# POWER_ANALOG.net
KiCad netlist of a schematic drawn in Altium Designer
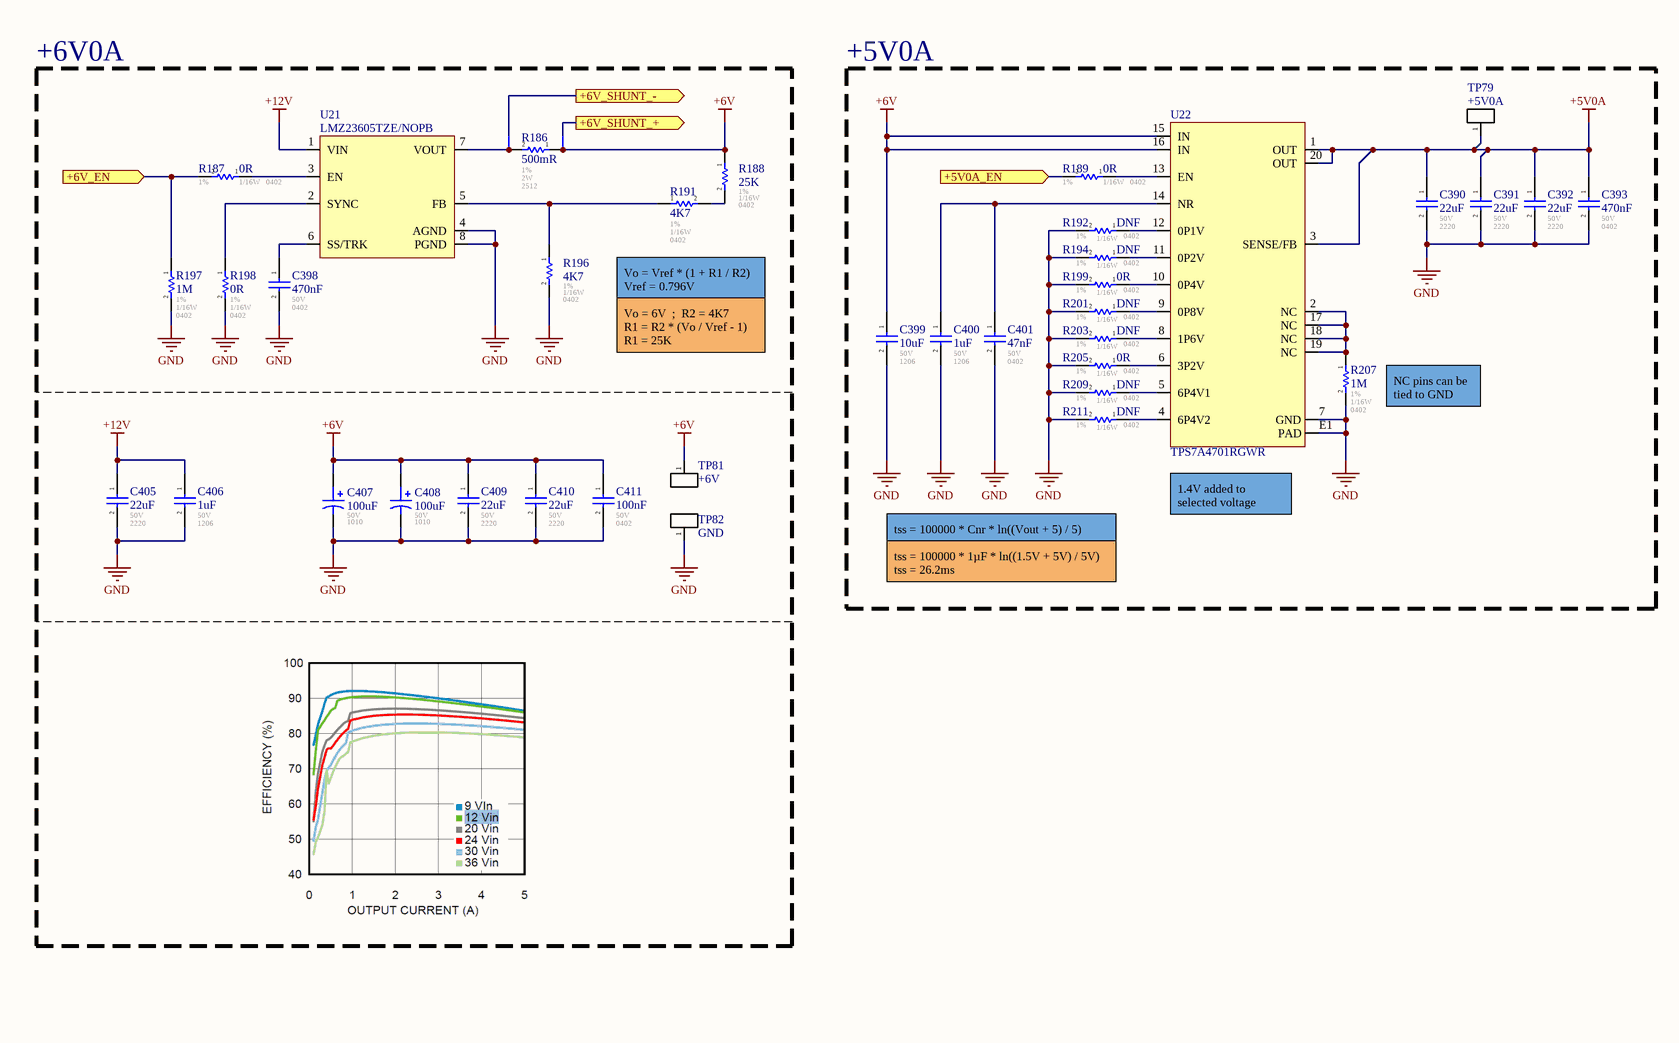
[diagram p0: POWER_ANALOG.SchDoc, top left]
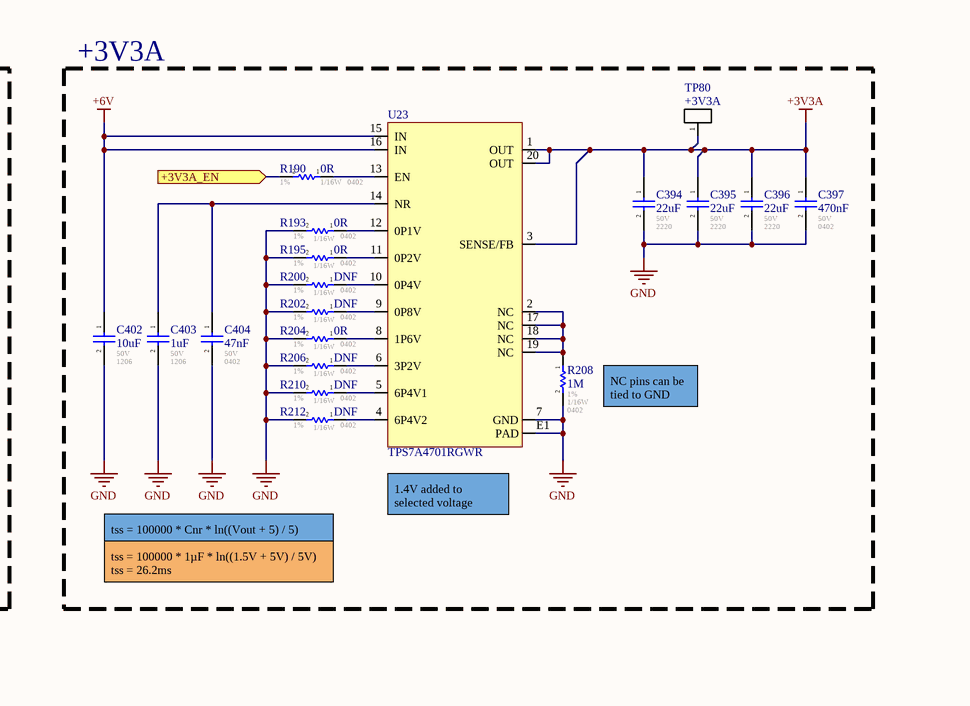
[diagram p1: POWER_ANALOG.SchDoc, top right]
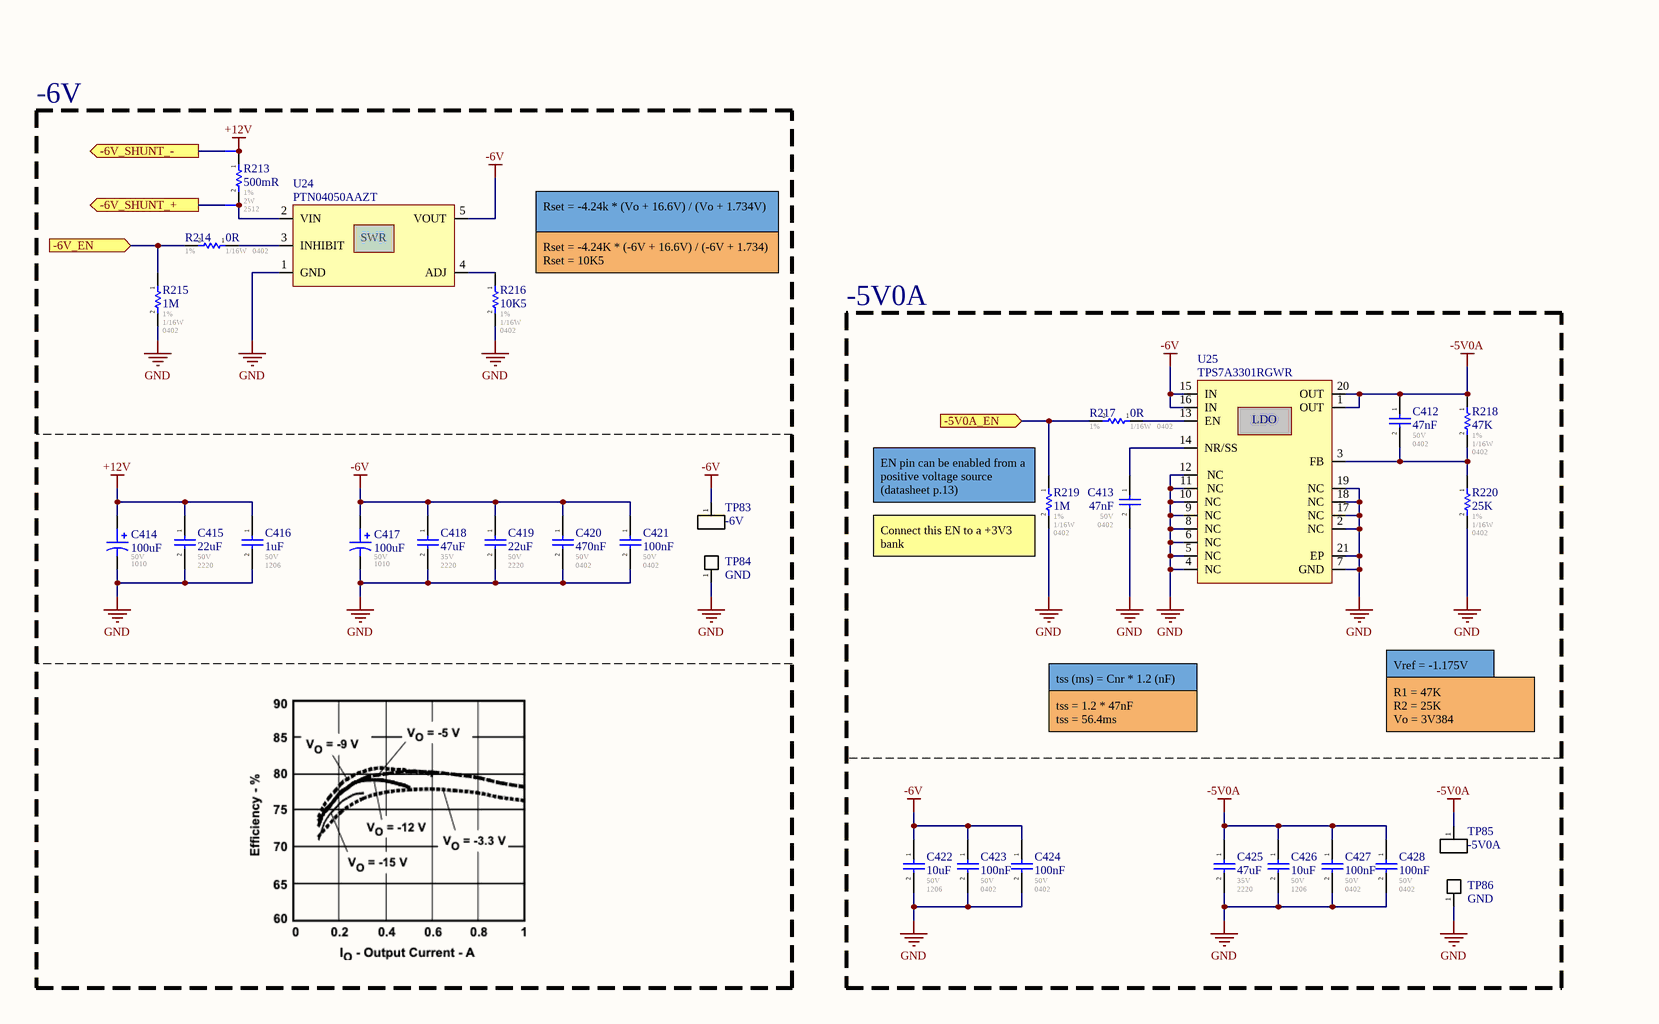
[diagram p2: POWER_ANALOG.SchDoc, bottom left]
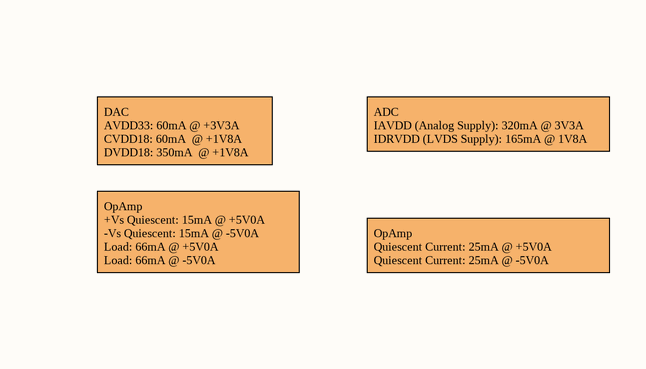
[diagram p3: POWER_ANALOG.SchDoc, bottom right]

(export (version "E")
  (design (tool "Eeschema 10.0.6"))
  (components
    (comp (ref "C390")
      (value "22uF")
      (footprint "2220")
      (description "CGA9P3X7R1H226M250KB\r\n2220 22uF 20% X7R Ceramic Capacitor")
      (fields
        (field (name "MFR") "TDK")
        (field (name "VOLTAGE - RATED") "50V")
        (field (name "TOLERANCE") "20%")
      )
      (libsource (lib "Symbols") (part "CAP_CER"))
    )
    (comp (ref "C391")
      (value "22uF")
      (footprint "2220")
      (description "CGA9P3X7R1H226M250KB\r\n2220 22uF 20% X7R Ceramic Capacitor")
      (fields
        (field (name "MFR") "TDK")
        (field (name "VOLTAGE - RATED") "50V")
        (field (name "TOLERANCE") "20%")
      )
      (libsource (lib "Symbols") (part "CAP_CER"))
    )
    (comp (ref "C392")
      (value "22uF")
      (footprint "2220")
      (description "CGA9P3X7R1H226M250KB\r\n2220 22uF 20% X7R Ceramic Capacitor")
      (fields
        (field (name "MFR") "TDK")
        (field (name "VOLTAGE - RATED") "50V")
        (field (name "TOLERANCE") "20%")
      )
      (libsource (lib "Symbols") (part "CAP_CER"))
    )
    (comp (ref "C393")
      (value "470nF")
      (footprint "0402")
      (description "CGA3E3X7R1H474K080AB\r\n0603 470nF 10% X7R Ceramic Capacitor")
      (fields
        (field (name "MFR") "TDK")
        (field (name "PART#") "CGA3E3X7R1H474K080AB")
        (field (name "VOLTAGE - RATED") "50V")
      )
      (libsource (lib "Symbols") (part "CAP_CER"))
    )
    (comp (ref "C394")
      (value "22uF")
      (footprint "2220")
      (description "CGA9P3X7R1H226M250KB\r\n2220 22uF 20% X7R Ceramic Capacitor")
      (fields
        (field (name "MFR") "TDK")
        (field (name "VOLTAGE - RATED") "50V")
        (field (name "TOLERANCE") "20%")
      )
      (libsource (lib "Symbols") (part "CAP_CER"))
    )
    (comp (ref "C395")
      (value "22uF")
      (footprint "2220")
      (description "CGA9P3X7R1H226M250KB\r\n2220 22uF 20% X7R Ceramic Capacitor")
      (fields
        (field (name "MFR") "TDK")
        (field (name "VOLTAGE - RATED") "50V")
        (field (name "TOLERANCE") "20%")
      )
      (libsource (lib "Symbols") (part "CAP_CER"))
    )
    (comp (ref "C396")
      (value "22uF")
      (footprint "2220")
      (description "CGA9P3X7R1H226M250KB\r\n2220 22uF 20% X7R Ceramic Capacitor")
      (fields
        (field (name "MFR") "TDK")
        (field (name "VOLTAGE - RATED") "50V")
        (field (name "TOLERANCE") "20%")
      )
      (libsource (lib "Symbols") (part "CAP_CER"))
    )
    (comp (ref "C397")
      (value "470nF")
      (footprint "0402")
      (description "CGA3E3X7R1H474K080AB\r\n0603 470nF 10% X7R Ceramic Capacitor")
      (fields
        (field (name "MFR") "TDK")
        (field (name "PART#") "CGA3E3X7R1H474K080AB")
        (field (name "VOLTAGE - RATED") "50V")
      )
      (libsource (lib "Symbols") (part "CAP_CER"))
    )
    (comp (ref "C398")
      (value "470nF")
      (footprint "0402")
      (description "CGA3E3X7R1H474K080AB\r\n0603 470nF 10% X7R Ceramic Capacitor")
      (fields
        (field (name "MFR") "TDK")
        (field (name "PART#") "CGA3E3X7R1H474K080AB")
        (field (name "VOLTAGE - RATED") "50V")
      )
      (libsource (lib "Symbols") (part "CAP_CER"))
    )
    (comp (ref "C399")
      (value "10uF")
      (footprint "1206")
      (description "GRT31CR61H106KE01L\r\n1206 10uF 10% X5R Ceramic Capacitor")
      (fields
        (field (name "MFR") "Murata")
        (field (name "VOLTAGE - RATED") "50V")
        (field (name "TOLERANCE") "10%")
      )
      (libsource (lib "Symbols") (part "CAP_CER"))
    )
    (comp (ref "C400")
      (value "1uF")
      (footprint "1206")
      (description "GCJ31CR71H105KA12L\r\n1206 1uF 10% X7R Ceramic Capacitor")
      (fields
        (field (name "MFR") "Murata")
        (field (name "PART#") "GCJ31CR71H105KA12L")
        (field (name "VOLTAGE - RATED") "50V")
      )
      (libsource (lib "Symbols") (part "CAP_CER"))
    )
    (comp (ref "C401")
      (value "47nF")
      (footprint "0402")
      (description "GCM155R71H473KE02J\r\n0402 47nF 10% X7R Ceramic Capacitor")
      (fields
        (field (name "MFR") "Murata")
        (field (name "PART#") "GCM155R71H473KE02J")
        (field (name "VOLTAGE - RATED") "50V")
      )
      (libsource (lib "Symbols") (part "CAP_CER"))
    )
    (comp (ref "C402")
      (value "10uF")
      (footprint "1206")
      (description "GRT31CR61H106KE01L\r\n1206 10uF 10% X5R Ceramic Capacitor")
      (fields
        (field (name "MFR") "Murata")
        (field (name "VOLTAGE - RATED") "50V")
        (field (name "TOLERANCE") "10%")
      )
      (libsource (lib "Symbols") (part "CAP_CER"))
    )
    (comp (ref "C403")
      (value "1uF")
      (footprint "1206")
      (description "GCJ31CR71H105KA12L\r\n1206 1uF 10% X7R Ceramic Capacitor")
      (fields
        (field (name "MFR") "Murata")
        (field (name "PART#") "GCJ31CR71H105KA12L")
        (field (name "VOLTAGE - RATED") "50V")
      )
      (libsource (lib "Symbols") (part "CAP_CER"))
    )
    (comp (ref "C404")
      (value "47nF")
      (footprint "0402")
      (description "GCM155R71H473KE02J\r\n0402 47nF 10% X7R Ceramic Capacitor")
      (fields
        (field (name "MFR") "Murata")
        (field (name "PART#") "GCM155R71H473KE02J")
        (field (name "VOLTAGE - RATED") "50V")
      )
      (libsource (lib "Symbols") (part "CAP_CER"))
    )
    (comp (ref "C405")
      (value "22uF")
      (footprint "2220")
      (description "CGA9P3X7R1H226M250KB\r\n2220 22uF 20% X7R Ceramic Capacitor")
      (fields
        (field (name "MFR") "TDK")
        (field (name "VOLTAGE - RATED") "50V")
        (field (name "TOLERANCE") "20%")
      )
      (libsource (lib "Symbols") (part "CAP_CER"))
    )
    (comp (ref "C406")
      (value "1uF")
      (footprint "1206")
      (description "GCJ31CR71H105KA12L\r\n1206 1uF 10% X7R Ceramic Capacitor")
      (fields
        (field (name "MFR") "Murata")
        (field (name "PART#") "GCJ31CR71H105KA12L")
        (field (name "VOLTAGE - RATED") "50V")
      )
      (libsource (lib "Symbols") (part "CAP_CER"))
    )
    (comp (ref "C407")
      (value "100uF")
      (footprint "CAP_ALU_1010_vishay")
      (description "CAP - ALU 100uF 20% 50V - 1010")
      (fields
        (field (name "MFG") "Vishay Dale")
        (field (name "MFG PART NUMBER") "MAL215099101E3")
        (field (name "VOLTAGE") "50V")
        (field (name "PACKAGE") "1010")
        (field (name "CREATEDBY") "Jonathan Bouchard")
      )
      (libsource (lib "S7CAS_LIB2023") (part "CAP_ALU_MAL215099101E3"))
    )
    (comp (ref "C408")
      (value "100uF")
      (footprint "CAP_ALU_1010_vishay")
      (description "CAP - ALU 100uF 20% 50V - 1010")
      (fields
        (field (name "MFG") "Vishay Dale")
        (field (name "MFG PART NUMBER") "MAL215099101E3")
        (field (name "VOLTAGE") "50V")
        (field (name "PACKAGE") "1010")
        (field (name "CREATEDBY") "Jonathan Bouchard")
      )
      (libsource (lib "S7CAS_LIB2023") (part "CAP_ALU_MAL215099101E3"))
    )
    (comp (ref "C409")
      (value "22uF")
      (footprint "2220")
      (description "CGA9P3X7R1H226M250KB\r\n2220 22uF 20% X7R Ceramic Capacitor")
      (fields
        (field (name "MFR") "TDK")
        (field (name "VOLTAGE - RATED") "50V")
        (field (name "TOLERANCE") "20%")
      )
      (libsource (lib "Symbols") (part "CAP_CER"))
    )
    (comp (ref "C410")
      (value "22uF")
      (footprint "2220")
      (description "CGA9P3X7R1H226M250KB\r\n2220 22uF 20% X7R Ceramic Capacitor")
      (fields
        (field (name "MFR") "TDK")
        (field (name "VOLTAGE - RATED") "50V")
        (field (name "TOLERANCE") "20%")
      )
      (libsource (lib "Symbols") (part "CAP_CER"))
    )
    (comp (ref "C411")
      (value "100nF")
      (footprint "0402")
      (description "GCM155R71H104KE02J\r\n0402 100nF 10% X7R Ceramic Capacitor")
      (fields
        (field (name "MFR") "Murata")
        (field (name "PART#") "GCM155R71H104KE02J")
        (field (name "VOLTAGE - RATED") "50V")
      )
      (libsource (lib "Symbols") (part "CAP_CER"))
    )
    (comp (ref "C412")
      (value "47nF")
      (footprint "0402")
      (description "GCM155R71H473KE02J\r\n0402 47nF 10% X7R Ceramic Capacitor")
      (fields
        (field (name "MFR") "Murata")
        (field (name "PART#") "GCM155R71H473KE02J")
        (field (name "VOLTAGE - RATED") "50V")
      )
      (libsource (lib "Symbols") (part "CAP_CER"))
    )
    (comp (ref "C413")
      (value "47nF")
      (footprint "0402")
      (description "GCM155R71H473KE02J\r\n0402 47nF 10% X7R Ceramic Capacitor")
      (fields
        (field (name "MFR") "Murata")
        (field (name "PART#") "GCM155R71H473KE02J")
        (field (name "VOLTAGE - RATED") "50V")
      )
      (libsource (lib "Symbols") (part "CAP_CER"))
    )
    (comp (ref "C414")
      (value "100uF")
      (footprint "CAP_ALU_1010_vishay")
      (description "CAP - ALU 100uF 20% 50V - 1010")
      (fields
        (field (name "MFG") "Vishay Dale")
        (field (name "MFG PART NUMBER") "MAL215099101E3")
        (field (name "VOLTAGE") "50V")
        (field (name "PACKAGE") "1010")
        (field (name "CREATEDBY") "Jonathan Bouchard")
      )
      (libsource (lib "S7CAS_LIB2023") (part "CAP_ALU_MAL215099101E3"))
    )
    (comp (ref "C415")
      (value "22uF")
      (footprint "2220")
      (description "CGA9P3X7R1H226M250KB\r\n2220 22uF 20% X7R Ceramic Capacitor")
      (fields
        (field (name "MFR") "TDK")
        (field (name "VOLTAGE - RATED") "50V")
        (field (name "TOLERANCE") "20%")
      )
      (libsource (lib "Symbols") (part "CAP_CER"))
    )
    (comp (ref "C416")
      (value "1uF")
      (footprint "1206")
      (description "GCJ31CR71H105KA12L\r\n1206 1uF 10% X7R Ceramic Capacitor")
      (fields
        (field (name "MFR") "Murata")
        (field (name "PART#") "GCJ31CR71H105KA12L")
        (field (name "VOLTAGE - RATED") "50V")
      )
      (libsource (lib "Symbols") (part "CAP_CER"))
    )
    (comp (ref "C417")
      (value "100uF")
      (footprint "CAP_ALU_1010_vishay")
      (description "CAP - ALU 100uF 20% 50V - 1010")
      (fields
        (field (name "MFG") "Vishay Dale")
        (field (name "MFG PART NUMBER") "MAL215099101E3")
        (field (name "VOLTAGE") "50V")
        (field (name "PACKAGE") "1010")
        (field (name "CREATEDBY") "Jonathan Bouchard")
      )
      (libsource (lib "S7CAS_LIB2023") (part "CAP_ALU_MAL215099101E3"))
    )
    (comp (ref "C418")
      (value "47uF")
      (footprint "2220")
      (description "CGA9N1X7R1V476M230KC\r\n2220 47uF 20% X7R Ceramic Capacitor")
      (fields
        (field (name "MFR") "TDK")
        (field (name "VOLTAGE - RATED") "35V")
        (field (name "TOLERANCE") "20%")
      )
      (libsource (lib "Symbols") (part "CAP_CER"))
    )
    (comp (ref "C419")
      (value "22uF")
      (footprint "2220")
      (description "CGA9P3X7R1H226M250KB\r\n2220 22uF 20% X7R Ceramic Capacitor")
      (fields
        (field (name "MFR") "TDK")
        (field (name "VOLTAGE - RATED") "50V")
        (field (name "TOLERANCE") "20%")
      )
      (libsource (lib "Symbols") (part "CAP_CER"))
    )
    (comp (ref "C420")
      (value "470nF")
      (footprint "0402")
      (description "CGA3E3X7R1H474K080AB\r\n0603 470nF 10% X7R Ceramic Capacitor")
      (fields
        (field (name "MFR") "TDK")
        (field (name "PART#") "CGA3E3X7R1H474K080AB")
        (field (name "VOLTAGE - RATED") "50V")
      )
      (libsource (lib "Symbols") (part "CAP_CER"))
    )
    (comp (ref "C421")
      (value "100nF")
      (footprint "0402")
      (description "GCM155R71H104KE02J\r\n0402 100nF 10% X7R Ceramic Capacitor")
      (fields
        (field (name "MFR") "Murata")
        (field (name "PART#") "GCM155R71H104KE02J")
        (field (name "VOLTAGE - RATED") "50V")
      )
      (libsource (lib "Symbols") (part "CAP_CER"))
    )
    (comp (ref "C422")
      (value "10uF")
      (footprint "1206")
      (description "GRT31CR61H106KE01L\r\n1206 10uF 10% X5R Ceramic Capacitor")
      (fields
        (field (name "MFR") "Murata")
        (field (name "VOLTAGE - RATED") "50V")
        (field (name "TOLERANCE") "10%")
      )
      (libsource (lib "Symbols") (part "CAP_CER"))
    )
    (comp (ref "C423")
      (value "100nF")
      (footprint "0402")
      (description "GCM155R71H104KE02J\r\n0402 100nF 10% X7R Ceramic Capacitor")
      (fields
        (field (name "MFR") "Murata")
        (field (name "PART#") "GCM155R71H104KE02J")
        (field (name "VOLTAGE - RATED") "50V")
      )
      (libsource (lib "Symbols") (part "CAP_CER"))
    )
    (comp (ref "C424")
      (value "100nF")
      (footprint "0402")
      (description "GCM155R71H104KE02J\r\n0402 100nF 10% X7R Ceramic Capacitor")
      (fields
        (field (name "MFR") "Murata")
        (field (name "PART#") "GCM155R71H104KE02J")
        (field (name "VOLTAGE - RATED") "50V")
      )
      (libsource (lib "Symbols") (part "CAP_CER"))
    )
    (comp (ref "C425")
      (value "47uF")
      (footprint "2220")
      (description "CGA9N1X7R1V476M230KC\r\n2220 47uF 20% X7R Ceramic Capacitor")
      (fields
        (field (name "MFR") "TDK")
        (field (name "VOLTAGE - RATED") "35V")
        (field (name "TOLERANCE") "20%")
      )
      (libsource (lib "Symbols") (part "CAP_CER"))
    )
    (comp (ref "C426")
      (value "10uF")
      (footprint "1206")
      (description "GRT31CR61H106KE01L\r\n1206 10uF 10% X5R Ceramic Capacitor")
      (fields
        (field (name "MFR") "Murata")
        (field (name "VOLTAGE - RATED") "50V")
        (field (name "TOLERANCE") "10%")
      )
      (libsource (lib "Symbols") (part "CAP_CER"))
    )
    (comp (ref "C427")
      (value "100nF")
      (footprint "0402")
      (description "GCM155R71H104KE02J\r\n0402 100nF 10% X7R Ceramic Capacitor")
      (fields
        (field (name "MFR") "Murata")
        (field (name "PART#") "GCM155R71H104KE02J")
        (field (name "VOLTAGE - RATED") "50V")
      )
      (libsource (lib "Symbols") (part "CAP_CER"))
    )
    (comp (ref "C428")
      (value "100nF")
      (footprint "0402")
      (description "GCM155R71H104KE02J\r\n0402 100nF 10% X7R Ceramic Capacitor")
      (fields
        (field (name "MFR") "Murata")
        (field (name "PART#") "GCM155R71H104KE02J")
        (field (name "VOLTAGE - RATED") "50V")
      )
      (libsource (lib "Symbols") (part "CAP_CER"))
    )
    (comp (ref "NT40")
      (value "Net Tie")
      (footprint "NETTIE_5")
      (libsource (lib "Symbols") (part "NET_TIE_SMALL"))
    )
    (comp (ref "NT41")
      (value "Net Tie")
      (footprint "NETTIE_5")
      (libsource (lib "Symbols") (part "NET_TIE_SMALL"))
    )
    (comp (ref "NT42")
      (value "Net Tie")
      (footprint "NETTIE_5")
      (libsource (lib "Symbols") (part "NET_TIE_SMALL"))
    )
    (comp (ref "NT43")
      (value "Net Tie")
      (footprint "NETTIE_5")
      (libsource (lib "Symbols") (part "NET_TIE_SMALL"))
    )
    (comp (ref "R186")
      (value "500mR")
      (footprint "RES_2512")
      (fields
        (field (name "PART #") "CSRN2512FKR500")
        (field (name "TOLERANCE") "1%")
        (field (name "POWER") "2W")
        (field (name "PACKAGE / CASE") "2512")
      )
      (libsource (lib "Symbols") (part "RESISTOR"))
    )
    (comp (ref "R187")
      (value "0R")
      (footprint "RES_0402")
      (fields
        (field (name "TOLERANCE") "1%")
        (field (name "POWER") "1/16W")
        (field (name "PACKAGE / CASE") "0402")
      )
      (libsource (lib "Symbols") (part "RESISTOR"))
    )
    (comp (ref "R188")
      (value "25K")
      (footprint "RES_0402")
      (fields
        (field (name "TOLERANCE") "1%")
        (field (name "POWER") "1/16W")
        (field (name "PACKAGE / CASE") "0402")
      )
      (libsource (lib "Symbols") (part "RESISTOR"))
    )
    (comp (ref "R189")
      (value "0R")
      (footprint "RES_0402")
      (fields
        (field (name "TOLERANCE") "1%")
        (field (name "POWER") "1/16W")
        (field (name "PACKAGE / CASE") "0402")
      )
      (libsource (lib "Symbols") (part "RESISTOR"))
    )
    (comp (ref "R190")
      (value "0R")
      (footprint "RES_0402")
      (fields
        (field (name "TOLERANCE") "1%")
        (field (name "POWER") "1/16W")
        (field (name "PACKAGE / CASE") "0402")
      )
      (libsource (lib "Symbols") (part "RESISTOR"))
    )
    (comp (ref "R191")
      (value "4K7")
      (footprint "RES_0402")
      (fields
        (field (name "TOLERANCE") "1%")
        (field (name "POWER") "1/16W")
        (field (name "PACKAGE / CASE") "0402")
      )
      (libsource (lib "Symbols") (part "RESISTOR"))
    )
    (comp (ref "R192")
      (value "DNF")
      (footprint "RES_0402")
      (fields
        (field (name "TOLERANCE") "1%")
        (field (name "POWER") "1/16W")
        (field (name "PACKAGE / CASE") "0402")
      )
      (libsource (lib "Symbols") (part "RESISTOR"))
    )
    (comp (ref "R193")
      (value "0R")
      (footprint "RES_0402")
      (fields
        (field (name "TOLERANCE") "1%")
        (field (name "POWER") "1/16W")
        (field (name "PACKAGE / CASE") "0402")
      )
      (libsource (lib "Symbols") (part "RESISTOR"))
    )
    (comp (ref "R194")
      (value "DNF")
      (footprint "RES_0402")
      (fields
        (field (name "TOLERANCE") "1%")
        (field (name "POWER") "1/16W")
        (field (name "PACKAGE / CASE") "0402")
      )
      (libsource (lib "Symbols") (part "RESISTOR"))
    )
    (comp (ref "R195")
      (value "0R")
      (footprint "RES_0402")
      (fields
        (field (name "TOLERANCE") "1%")
        (field (name "POWER") "1/16W")
        (field (name "PACKAGE / CASE") "0402")
      )
      (libsource (lib "Symbols") (part "RESISTOR"))
    )
    (comp (ref "R196")
      (value "4K7")
      (footprint "RES_0402")
      (fields
        (field (name "TOLERANCE") "1%")
        (field (name "POWER") "1/16W")
        (field (name "PACKAGE / CASE") "0402")
      )
      (libsource (lib "Symbols") (part "RESISTOR"))
    )
    (comp (ref "R197")
      (value "1M")
      (footprint "RES_0402")
      (description "1M 0402 1% 1/16W Resistor")
      (fields
        (field (name "TOLERANCE") "1%")
        (field (name "POWER") "1/16W")
        (field (name "PACKAGE / CASE") "0402")
      )
      (libsource (lib "Symbols") (part "RESISTOR"))
    )
    (comp (ref "R198")
      (value "0R")
      (footprint "RES_0402")
      (fields
        (field (name "TOLERANCE") "1%")
        (field (name "POWER") "1/16W")
        (field (name "PACKAGE / CASE") "0402")
      )
      (libsource (lib "Symbols") (part "RESISTOR"))
    )
    (comp (ref "R199")
      (value "0R")
      (footprint "RES_0402")
      (fields
        (field (name "TOLERANCE") "1%")
        (field (name "POWER") "1/16W")
        (field (name "PACKAGE / CASE") "0402")
      )
      (libsource (lib "Symbols") (part "RESISTOR"))
    )
    (comp (ref "R200")
      (value "DNF")
      (footprint "RES_0402")
      (fields
        (field (name "TOLERANCE") "1%")
        (field (name "POWER") "1/16W")
        (field (name "PACKAGE / CASE") "0402")
      )
      (libsource (lib "Symbols") (part "RESISTOR"))
    )
    (comp (ref "R201")
      (value "DNF")
      (footprint "RES_0402")
      (fields
        (field (name "TOLERANCE") "1%")
        (field (name "POWER") "1/16W")
        (field (name "PACKAGE / CASE") "0402")
      )
      (libsource (lib "Symbols") (part "RESISTOR"))
    )
    (comp (ref "R202")
      (value "DNF")
      (footprint "RES_0402")
      (fields
        (field (name "TOLERANCE") "1%")
        (field (name "POWER") "1/16W")
        (field (name "PACKAGE / CASE") "0402")
      )
      (libsource (lib "Symbols") (part "RESISTOR"))
    )
    (comp (ref "R203")
      (value "DNF")
      (footprint "RES_0402")
      (fields
        (field (name "TOLERANCE") "1%")
        (field (name "POWER") "1/16W")
        (field (name "PACKAGE / CASE") "0402")
      )
      (libsource (lib "Symbols") (part "RESISTOR"))
    )
    (comp (ref "R204")
      (value "0R")
      (footprint "RES_0402")
      (fields
        (field (name "TOLERANCE") "1%")
        (field (name "POWER") "1/16W")
        (field (name "PACKAGE / CASE") "0402")
      )
      (libsource (lib "Symbols") (part "RESISTOR"))
    )
    (comp (ref "R205")
      (value "0R")
      (footprint "RES_0402")
      (fields
        (field (name "TOLERANCE") "1%")
        (field (name "POWER") "1/16W")
        (field (name "PACKAGE / CASE") "0402")
      )
      (libsource (lib "Symbols") (part "RESISTOR"))
    )
    (comp (ref "R206")
      (value "DNF")
      (footprint "RES_0402")
      (fields
        (field (name "TOLERANCE") "1%")
        (field (name "POWER") "1/16W")
        (field (name "PACKAGE / CASE") "0402")
      )
      (libsource (lib "Symbols") (part "RESISTOR"))
    )
    (comp (ref "R207")
      (value "1M")
      (footprint "RES_0402")
      (description "1M 0402 1% 1/16W Resistor")
      (fields
        (field (name "TOLERANCE") "1%")
        (field (name "POWER") "1/16W")
        (field (name "PACKAGE / CASE") "0402")
      )
      (libsource (lib "Symbols") (part "RESISTOR"))
    )
    (comp (ref "R208")
      (value "1M")
      (footprint "RES_0402")
      (description "1M 0402 1% 1/16W Resistor")
      (fields
        (field (name "TOLERANCE") "1%")
        (field (name "POWER") "1/16W")
        (field (name "PACKAGE / CASE") "0402")
      )
      (libsource (lib "Symbols") (part "RESISTOR"))
    )
    (comp (ref "R209")
      (value "DNF")
      (footprint "RES_0402")
      (fields
        (field (name "TOLERANCE") "1%")
        (field (name "POWER") "1/16W")
        (field (name "PACKAGE / CASE") "0402")
      )
      (libsource (lib "Symbols") (part "RESISTOR"))
    )
    (comp (ref "R210")
      (value "DNF")
      (footprint "RES_0402")
      (fields
        (field (name "TOLERANCE") "1%")
        (field (name "POWER") "1/16W")
        (field (name "PACKAGE / CASE") "0402")
      )
      (libsource (lib "Symbols") (part "RESISTOR"))
    )
    (comp (ref "R211")
      (value "DNF")
      (footprint "RES_0402")
      (fields
        (field (name "TOLERANCE") "1%")
        (field (name "POWER") "1/16W")
        (field (name "PACKAGE / CASE") "0402")
      )
      (libsource (lib "Symbols") (part "RESISTOR"))
    )
    (comp (ref "R212")
      (value "DNF")
      (footprint "RES_0402")
      (fields
        (field (name "TOLERANCE") "1%")
        (field (name "POWER") "1/16W")
        (field (name "PACKAGE / CASE") "0402")
      )
      (libsource (lib "Symbols") (part "RESISTOR"))
    )
    (comp (ref "R213")
      (value "500mR")
      (footprint "RES_2512")
      (fields
        (field (name "PART #") "CSRN2512FKR500")
        (field (name "TOLERANCE") "1%")
        (field (name "POWER") "2W")
        (field (name "PACKAGE / CASE") "2512")
      )
      (libsource (lib "Symbols") (part "RESISTOR"))
    )
    (comp (ref "R214")
      (value "0R")
      (footprint "RES_0402")
      (fields
        (field (name "TOLERANCE") "1%")
        (field (name "POWER") "1/16W")
        (field (name "PACKAGE / CASE") "0402")
      )
      (libsource (lib "Symbols") (part "RESISTOR"))
    )
    (comp (ref "R215")
      (value "1M")
      (footprint "RES_0402")
      (description "1M 0402 1% 1/16W Resistor")
      (fields
        (field (name "TOLERANCE") "1%")
        (field (name "POWER") "1/16W")
        (field (name "PACKAGE / CASE") "0402")
      )
      (libsource (lib "Symbols") (part "RESISTOR"))
    )
    (comp (ref "R216")
      (value "10K5")
      (footprint "RES_0402")
      (fields
        (field (name "TOLERANCE") "1%")
        (field (name "POWER") "1/16W")
        (field (name "PACKAGE / CASE") "0402")
      )
      (libsource (lib "Symbols") (part "RESISTOR"))
    )
    (comp (ref "R217")
      (value "0R")
      (footprint "RES_0402")
      (fields
        (field (name "TOLERANCE") "1%")
        (field (name "POWER") "1/16W")
        (field (name "PACKAGE / CASE") "0402")
      )
      (libsource (lib "Symbols") (part "RESISTOR"))
    )
    (comp (ref "R218")
      (value "47K")
      (footprint "RES_0402")
      (fields
        (field (name "TOLERANCE") "1%")
        (field (name "POWER") "1/16W")
        (field (name "PACKAGE / CASE") "0402")
      )
      (libsource (lib "Symbols") (part "RESISTOR"))
    )
    (comp (ref "R219")
      (value "1M")
      (footprint "RES_0402")
      (description "1M 0402 1% 1/16W Resistor")
      (fields
        (field (name "TOLERANCE") "1%")
        (field (name "POWER") "1/16W")
        (field (name "PACKAGE / CASE") "0402")
      )
      (libsource (lib "Symbols") (part "RESISTOR"))
    )
    (comp (ref "R220")
      (value "25K")
      (footprint "RES_0402")
      (fields
        (field (name "TOLERANCE") "1%")
        (field (name "POWER") "1/16W")
        (field (name "PACKAGE / CASE") "0402")
      )
      (libsource (lib "Symbols") (part "RESISTOR"))
    )
    (comp (ref "TP79")
      (value "+5V0A")
      (footprint "TP_HOLE")
      (description "Test Point")
      (libsource (lib "Symbols") (part "TESTPOINT"))
    )
    (comp (ref "TP80")
      (value "+3V3A")
      (footprint "TP_HOLE")
      (description "Test Point")
      (libsource (lib "Symbols") (part "TESTPOINT"))
    )
    (comp (ref "TP81")
      (value "+6V")
      (footprint "TP_HOLE")
      (description "Test Point")
      (libsource (lib "Symbols") (part "TESTPOINT"))
    )
    (comp (ref "TP82")
      (value "GND")
      (footprint "TP_HOLE")
      (description "Test Point")
      (libsource (lib "Symbols") (part "TESTPOINT"))
    )
    (comp (ref "TP83")
      (value "-6V")
      (footprint "TP_HOLE")
      (description "Test Point")
      (libsource (lib "Symbols") (part "TESTPOINT"))
    )
    (comp (ref "TP84")
      (value "GND")
      (footprint "TP_PAD")
      (description "Test Point")
      (libsource (lib "Symbols") (part "TESTPOINT_PAD"))
    )
    (comp (ref "TP85")
      (value "-5V0A")
      (footprint "TP_HOLE")
      (description "Test Point")
      (libsource (lib "Symbols") (part "TESTPOINT"))
    )
    (comp (ref "TP86")
      (value "GND")
      (footprint "TP_PAD")
      (description "Test Point")
      (libsource (lib "Symbols") (part "TESTPOINT_PAD"))
    )
    (comp (ref "U21")
      (value "LMZ23605TZE/NOPB")
      (footprint "REG_SWR_LMZ23605TZE/NOPB")
      (description "REG - IC BUCK SYNC 36V 5A - TO-PMOD-7")
      (fields
        (field (name "CREATEDBY/DATE") "Arnaud Samson - 05/07/18")
        (field (name "VERIFIEDBY") "Jonathan Bouchard 2018-07-13")
      )
      (libsource (lib "S7CAS_LIB2023") (part "REG_SWR_LMZ23605TZE/NOPB"))
    )
    (comp (ref "U22")
      (value "TPS7A4701RGWR")
      (footprint "REG_TPS7A4701RGWR")
      (description "REG - LINEAR POS ADJ 1A - 20VQFN")
      (fields
        (field (name "CREATEDBY/DATE") "L-P Gauthier / 2018-05-29")
        (field (name "VERIFIEDBY") "Caroline Paulin - 28 sept 2018")
      )
      (libsource (lib "S7CAS_LIB2023") (part "REG_LDO_TPS7A4701RGWR"))
    )
    (comp (ref "U23")
      (value "TPS7A4701RGWR")
      (footprint "REG_TPS7A4701RGWR")
      (description "REG - LINEAR POS ADJ 1A - 20VQFN")
      (fields
        (field (name "CREATEDBY/DATE") "L-P Gauthier / 2018-05-29")
        (field (name "VERIFIEDBY") "Caroline Paulin - 28 sept 2018")
      )
      (libsource (lib "S7CAS_LIB2023") (part "REG_LDO_TPS7A4701RGWR"))
    )
    (comp (ref "U24")
      (value "PTN04050AAZT")
      (footprint "REG_SWR_PTN04050AAZT")
      (description "REG - SWR -15 ~ -3.3V 1A 6W - 5-SMD")
      (fields
        (field (name "CREATEDBY/DATE") "Ihsane Najahi 2019-09-25")
        (field (name "VERIFIEDBY") "C.Paulin (9-10-2019)")
      )
      (libsource (lib "S7CAS_LIB2023") (part "REG_SWR_PTN04050AAZT"))
    )
    (comp (ref "U25")
      (value "TPS7A3301RGWR")
      (footprint "REG_LDO_TPS7A3301RGWR")
      (description "REG - LDO Negative Adjustable 1 Output -1.18V-33V 1A -  20-VQFN (5x5)")
      (fields
        (field (name "CREATEDBY/DATE") "Keven Deslandes - 2018/10/11")
        (field (name "VERIFIEDBY") "Caroline Paulin - 11/12/2018")
      )
      (libsource (lib "S7CAS_LIB2023") (part "REG_LDO_TPS7A3301RGWR"))
    )
  )
  (nets
    (net (code "1") (name "+3V3A") (class "Default")
      (node (ref "C394") (pin "1") (pinfunction "1_1") (pintype "passive"))
      (node (ref "C395") (pin "1") (pinfunction "1_1") (pintype "passive"))
      (node (ref "C396") (pin "1") (pinfunction "1_1") (pintype "passive"))
      (node (ref "C397") (pin "1") (pinfunction "1_1") (pintype "passive"))
      (node (ref "TP80") (pin "1") (pinfunction "A_1") (pintype "passive"))
      (node (ref "U23") (pin "1") (pinfunction "OUT_1") (pintype "passive"))
      (node (ref "U23") (pin "20") (pinfunction "OUT_20") (pintype "passive"))
      (node (ref "U23") (pin "3") (pinfunction "SENSE/FB_3") (pintype "passive"))
    )
    (net (code "2") (name "+5V0A") (class "Default")
      (node (ref "C390") (pin "1") (pinfunction "1_1") (pintype "passive"))
      (node (ref "C391") (pin "1") (pinfunction "1_1") (pintype "passive"))
      (node (ref "C392") (pin "1") (pinfunction "1_1") (pintype "passive"))
      (node (ref "C393") (pin "1") (pinfunction "1_1") (pintype "passive"))
      (node (ref "TP79") (pin "1") (pinfunction "A_1") (pintype "passive"))
      (node (ref "U22") (pin "1") (pinfunction "OUT_1") (pintype "passive"))
      (node (ref "U22") (pin "20") (pinfunction "OUT_20") (pintype "passive"))
      (node (ref "U22") (pin "3") (pinfunction "SENSE/FB_3") (pintype "passive"))
    )
    (net (code "3") (name "+6V") (class "Default")
      (node (ref "C399") (pin "1") (pinfunction "1_1") (pintype "passive"))
      (node (ref "C402") (pin "1") (pinfunction "1_1") (pintype "passive"))
      (node (ref "C407") (pin "1") (pinfunction "1_1") (pintype "passive"))
      (node (ref "C408") (pin "1") (pinfunction "1_1") (pintype "passive"))
      (node (ref "C409") (pin "1") (pinfunction "1_1") (pintype "passive"))
      (node (ref "C410") (pin "1") (pinfunction "1_1") (pintype "passive"))
      (node (ref "C411") (pin "1") (pinfunction "1_1") (pintype "passive"))
      (node (ref "NT41") (pin "1") (pinfunction "1_1") (pintype "passive"))
      (node (ref "R186") (pin "1") (pinfunction "1_1") (pintype "passive"))
      (node (ref "R188") (pin "1") (pinfunction "1_1") (pintype "passive"))
      (node (ref "TP81") (pin "1") (pinfunction "A_1") (pintype "passive"))
      (node (ref "U22") (pin "15") (pinfunction "IN_15") (pintype "passive"))
      (node (ref "U22") (pin "16") (pinfunction "IN_16") (pintype "passive"))
      (node (ref "U23") (pin "15") (pinfunction "IN_15") (pintype "passive"))
      (node (ref "U23") (pin "16") (pinfunction "IN_16") (pintype "passive"))
    )
    (net (code "4") (name "+12V") (class "Default")
      (node (ref "C405") (pin "1") (pinfunction "1_1") (pintype "passive"))
      (node (ref "C406") (pin "1") (pinfunction "1_1") (pintype "passive"))
      (node (ref "C414") (pin "1") (pinfunction "1_1") (pintype "passive"))
      (node (ref "C415") (pin "1") (pinfunction "1_1") (pintype "passive"))
      (node (ref "C416") (pin "1") (pinfunction "1_1") (pintype "passive"))
      (node (ref "NT42") (pin "1") (pinfunction "1_1") (pintype "passive"))
      (node (ref "R213") (pin "1") (pinfunction "1_1") (pintype "passive"))
      (node (ref "U21") (pin "1") (pinfunction "VIN_1") (pintype "passive"))
    )
    (net (code "5") (name "-5V0A") (class "Default")
      (node (ref "C412") (pin "1") (pinfunction "1_1") (pintype "passive"))
      (node (ref "C425") (pin "1") (pinfunction "1_1") (pintype "passive"))
      (node (ref "C426") (pin "1") (pinfunction "1_1") (pintype "passive"))
      (node (ref "C427") (pin "1") (pinfunction "1_1") (pintype "passive"))
      (node (ref "C428") (pin "1") (pinfunction "1_1") (pintype "passive"))
      (node (ref "R218") (pin "1") (pinfunction "1_1") (pintype "passive"))
      (node (ref "TP85") (pin "1") (pinfunction "A_1") (pintype "passive"))
      (node (ref "U25") (pin "1") (pinfunction "OUT_1") (pintype "passive"))
      (node (ref "U25") (pin "20") (pinfunction "OUT_20") (pintype "passive"))
    )
    (net (code "6") (name "-6V") (class "Default")
      (node (ref "C417") (pin "1") (pinfunction "1_1") (pintype "passive"))
      (node (ref "C418") (pin "1") (pinfunction "1_1") (pintype "passive"))
      (node (ref "C419") (pin "1") (pinfunction "1_1") (pintype "passive"))
      (node (ref "C420") (pin "1") (pinfunction "1_1") (pintype "passive"))
      (node (ref "C421") (pin "1") (pinfunction "1_1") (pintype "passive"))
      (node (ref "C422") (pin "1") (pinfunction "1_1") (pintype "passive"))
      (node (ref "C423") (pin "1") (pinfunction "1_1") (pintype "passive"))
      (node (ref "C424") (pin "1") (pinfunction "1_1") (pintype "passive"))
      (node (ref "TP83") (pin "1") (pinfunction "A_1") (pintype "passive"))
      (node (ref "U24") (pin "5") (pinfunction "VOUT_5") (pintype "passive"))
      (node (ref "U25") (pin "15") (pinfunction "IN_15") (pintype "passive"))
      (node (ref "U25") (pin "16") (pinfunction "IN_16") (pintype "passive"))
    )
    (net (code "7") (name "/+3V3A_EN") (class "Default")
      (node (ref "R190") (pin "2") (pinfunction "2_2") (pintype "passive"))
    )
    (net (code "8") (name "/+5V0A_EN") (class "Default")
      (node (ref "R189") (pin "2") (pinfunction "2_2") (pintype "passive"))
    )
    (net (code "9") (name "/+6V_EN") (class "Default")
      (node (ref "R187") (pin "2") (pinfunction "2_2") (pintype "passive"))
      (node (ref "R197") (pin "1") (pinfunction "1_1") (pintype "passive"))
    )
    (net (code "10") (name "/+6V_SHUNT_+") (class "Default")
      (node (ref "NT41") (pin "2") (pinfunction "2_2") (pintype "passive"))
    )
    (net (code "11") (name "/+6V_SHUNT_-") (class "Default")
      (node (ref "NT40") (pin "2") (pinfunction "2_2") (pintype "passive"))
    )
    (net (code "12") (name "/-5V0A_EN") (class "Default")
      (node (ref "R217") (pin "2") (pinfunction "2_2") (pintype "passive"))
      (node (ref "R219") (pin "1") (pinfunction "1_1") (pintype "passive"))
    )
    (net (code "13") (name "/-6V_EN") (class "Default")
      (node (ref "R214") (pin "2") (pinfunction "2_2") (pintype "passive"))
      (node (ref "R215") (pin "1") (pinfunction "1_1") (pintype "passive"))
    )
    (net (code "14") (name "/-6V_SHUNT_+") (class "Default")
      (node (ref "NT43") (pin "2") (pinfunction "2_2") (pintype "passive"))
    )
    (net (code "15") (name "/-6V_SHUNT_-") (class "Default")
      (node (ref "NT42") (pin "2") (pinfunction "2_2") (pintype "passive"))
    )
    (net (code "16") (name "GND") (class "Default")
      (node (ref "C390") (pin "2") (pinfunction "2_2") (pintype "passive"))
      (node (ref "C391") (pin "2") (pinfunction "2_2") (pintype "passive"))
      (node (ref "C392") (pin "2") (pinfunction "2_2") (pintype "passive"))
      (node (ref "C393") (pin "2") (pinfunction "2_2") (pintype "passive"))
      (node (ref "C394") (pin "2") (pinfunction "2_2") (pintype "passive"))
      (node (ref "C395") (pin "2") (pinfunction "2_2") (pintype "passive"))
      (node (ref "C396") (pin "2") (pinfunction "2_2") (pintype "passive"))
      (node (ref "C397") (pin "2") (pinfunction "2_2") (pintype "passive"))
      (node (ref "C398") (pin "2") (pinfunction "2_2") (pintype "passive"))
      (node (ref "C399") (pin "2") (pinfunction "2_2") (pintype "passive"))
      (node (ref "C400") (pin "2") (pinfunction "2_2") (pintype "passive"))
      (node (ref "C401") (pin "2") (pinfunction "2_2") (pintype "passive"))
      (node (ref "C402") (pin "2") (pinfunction "2_2") (pintype "passive"))
      (node (ref "C403") (pin "2") (pinfunction "2_2") (pintype "passive"))
      (node (ref "C404") (pin "2") (pinfunction "2_2") (pintype "passive"))
      (node (ref "C405") (pin "2") (pinfunction "2_2") (pintype "passive"))
      (node (ref "C406") (pin "2") (pinfunction "2_2") (pintype "passive"))
      (node (ref "C407") (pin "2") (pinfunction "2_2") (pintype "passive"))
      (node (ref "C408") (pin "2") (pinfunction "2_2") (pintype "passive"))
      (node (ref "C409") (pin "2") (pinfunction "2_2") (pintype "passive"))
      (node (ref "C410") (pin "2") (pinfunction "2_2") (pintype "passive"))
      (node (ref "C411") (pin "2") (pinfunction "2_2") (pintype "passive"))
      (node (ref "C413") (pin "2") (pinfunction "2_2") (pintype "passive"))
      (node (ref "C414") (pin "2") (pinfunction "2_2") (pintype "passive"))
      (node (ref "C415") (pin "2") (pinfunction "2_2") (pintype "passive"))
      (node (ref "C416") (pin "2") (pinfunction "2_2") (pintype "passive"))
      (node (ref "C417") (pin "2") (pinfunction "2_2") (pintype "passive"))
      (node (ref "C418") (pin "2") (pinfunction "2_2") (pintype "passive"))
      (node (ref "C419") (pin "2") (pinfunction "2_2") (pintype "passive"))
      (node (ref "C420") (pin "2") (pinfunction "2_2") (pintype "passive"))
      (node (ref "C421") (pin "2") (pinfunction "2_2") (pintype "passive"))
      (node (ref "C422") (pin "2") (pinfunction "2_2") (pintype "passive"))
      (node (ref "C423") (pin "2") (pinfunction "2_2") (pintype "passive"))
      (node (ref "C424") (pin "2") (pinfunction "2_2") (pintype "passive"))
      (node (ref "C425") (pin "2") (pinfunction "2_2") (pintype "passive"))
      (node (ref "C426") (pin "2") (pinfunction "2_2") (pintype "passive"))
      (node (ref "C427") (pin "2") (pinfunction "2_2") (pintype "passive"))
      (node (ref "C428") (pin "2") (pinfunction "2_2") (pintype "passive"))
      (node (ref "R192") (pin "2") (pinfunction "2_2") (pintype "passive"))
      (node (ref "R193") (pin "2") (pinfunction "2_2") (pintype "passive"))
      (node (ref "R194") (pin "2") (pinfunction "2_2") (pintype "passive"))
      (node (ref "R195") (pin "2") (pinfunction "2_2") (pintype "passive"))
      (node (ref "R196") (pin "2") (pinfunction "2_2") (pintype "passive"))
      (node (ref "R197") (pin "2") (pinfunction "2_2") (pintype "passive"))
      (node (ref "R198") (pin "2") (pinfunction "2_2") (pintype "passive"))
      (node (ref "R199") (pin "2") (pinfunction "2_2") (pintype "passive"))
      (node (ref "R200") (pin "2") (pinfunction "2_2") (pintype "passive"))
      (node (ref "R201") (pin "2") (pinfunction "2_2") (pintype "passive"))
      (node (ref "R202") (pin "2") (pinfunction "2_2") (pintype "passive"))
      (node (ref "R203") (pin "2") (pinfunction "2_2") (pintype "passive"))
      (node (ref "R204") (pin "2") (pinfunction "2_2") (pintype "passive"))
      (node (ref "R205") (pin "2") (pinfunction "2_2") (pintype "passive"))
      (node (ref "R206") (pin "2") (pinfunction "2_2") (pintype "passive"))
      (node (ref "R207") (pin "2") (pinfunction "2_2") (pintype "passive"))
      (node (ref "R208") (pin "2") (pinfunction "2_2") (pintype "passive"))
      (node (ref "R209") (pin "2") (pinfunction "2_2") (pintype "passive"))
      (node (ref "R210") (pin "2") (pinfunction "2_2") (pintype "passive"))
      (node (ref "R211") (pin "2") (pinfunction "2_2") (pintype "passive"))
      (node (ref "R212") (pin "2") (pinfunction "2_2") (pintype "passive"))
      (node (ref "R215") (pin "2") (pinfunction "2_2") (pintype "passive"))
      (node (ref "R216") (pin "2") (pinfunction "2_2") (pintype "passive"))
      (node (ref "R219") (pin "2") (pinfunction "2_2") (pintype "passive"))
      (node (ref "R220") (pin "2") (pinfunction "2_2") (pintype "passive"))
      (node (ref "TP82") (pin "1") (pinfunction "A_1") (pintype "passive"))
      (node (ref "TP84") (pin "1") (pinfunction "A_1") (pintype "passive"))
      (node (ref "TP86") (pin "1") (pinfunction "A_1") (pintype "passive"))
      (node (ref "U21") (pin "4") (pinfunction "AGND_4") (pintype "passive"))
      (node (ref "U21") (pin "8") (pinfunction "PGND_8") (pintype "passive"))
      (node (ref "U22") (pin "7") (pinfunction "GND_7") (pintype "passive"))
      (node (ref "U22") (pin "E1") (pinfunction "PAD_E1") (pintype "passive"))
      (node (ref "U23") (pin "7") (pinfunction "GND_7") (pintype "passive"))
      (node (ref "U23") (pin "E1") (pinfunction "PAD_E1") (pintype "passive"))
      (node (ref "U24") (pin "1") (pinfunction "GND_1") (pintype "passive"))
      (node (ref "U25") (pin "10") (pinfunction "NC_10") (pintype "passive"))
      (node (ref "U25") (pin "11") (pinfunction "NC_11") (pintype "passive"))
      (node (ref "U25") (pin "12") (pinfunction "NC_12") (pintype "passive"))
      (node (ref "U25") (pin "17") (pinfunction "NC_17") (pintype "passive"))
      (node (ref "U25") (pin "18") (pinfunction "NC_18") (pintype "passive"))
      (node (ref "U25") (pin "19") (pinfunction "NC_19") (pintype "passive"))
      (node (ref "U25") (pin "2") (pinfunction "NC_2") (pintype "passive"))
      (node (ref "U25") (pin "21") (pinfunction "EP_21") (pintype "passive"))
      (node (ref "U25") (pin "4") (pinfunction "NC_4") (pintype "passive"))
      (node (ref "U25") (pin "5") (pinfunction "NC_5") (pintype "passive"))
      (node (ref "U25") (pin "6") (pinfunction "NC_6") (pintype "passive"))
      (node (ref "U25") (pin "7") (pinfunction "GND_7") (pintype "passive"))
      (node (ref "U25") (pin "8") (pinfunction "NC_8") (pintype "passive"))
      (node (ref "U25") (pin "9") (pinfunction "NC_9") (pintype "passive"))
    )
    (net (code "17") (name "Net-(R188-Pad2)") (class "Default")
      (node (ref "R188") (pin "2") (pinfunction "2_2") (pintype "passive"))
      (node (ref "R191") (pin "2") (pinfunction "2_2") (pintype "passive"))
    )
    (net (code "18") (name "Net-(R207-Pad1)") (class "Default")
      (node (ref "R207") (pin "1") (pinfunction "1_1") (pintype "passive"))
      (node (ref "U22") (pin "17") (pinfunction "NC_17") (pintype "passive"))
      (node (ref "U22") (pin "18") (pinfunction "NC_18") (pintype "passive"))
      (node (ref "U22") (pin "19") (pinfunction "NC_19") (pintype "passive"))
      (node (ref "U22") (pin "2") (pinfunction "NC_2") (pintype "passive"))
    )
    (net (code "19") (name "Net-(R208-Pad1)") (class "Default")
      (node (ref "R208") (pin "1") (pinfunction "1_1") (pintype "passive"))
      (node (ref "U23") (pin "17") (pinfunction "NC_17") (pintype "passive"))
      (node (ref "U23") (pin "18") (pinfunction "NC_18") (pintype "passive"))
      (node (ref "U23") (pin "19") (pinfunction "NC_19") (pintype "passive"))
      (node (ref "U23") (pin "2") (pinfunction "NC_2") (pintype "passive"))
    )
    (net (code "20") (name "Net-(U21-EN)") (class "Default")
      (node (ref "R187") (pin "1") (pinfunction "1_1") (pintype "passive"))
      (node (ref "U21") (pin "3") (pinfunction "EN_3") (pintype "passive"))
    )
    (net (code "21") (name "Net-(U21-FB)") (class "Default")
      (node (ref "R191") (pin "1") (pinfunction "1_1") (pintype "passive"))
      (node (ref "R196") (pin "1") (pinfunction "1_1") (pintype "passive"))
      (node (ref "U21") (pin "5") (pinfunction "FB_5") (pintype "passive"))
    )
    (net (code "22") (name "Net-(U21-SS{slash}TRK)") (class "Default")
      (node (ref "C398") (pin "1") (pinfunction "1_1") (pintype "passive"))
      (node (ref "U21") (pin "6") (pinfunction "SS/TRK_6") (pintype "passive"))
    )
    (net (code "23") (name "Net-(U21-SYNC)") (class "Default")
      (node (ref "R198") (pin "1") (pinfunction "1_1") (pintype "passive"))
      (node (ref "U21") (pin "2") (pinfunction "SYNC_2") (pintype "passive"))
    )
    (net (code "24") (name "Net-(U21-VOUT)") (class "Default")
      (node (ref "NT40") (pin "1") (pinfunction "1_1") (pintype "passive"))
      (node (ref "R186") (pin "2") (pinfunction "2_2") (pintype "passive"))
      (node (ref "U21") (pin "7") (pinfunction "VOUT_7") (pintype "passive"))
    )
    (net (code "25") (name "Net-(U22-0P1V)") (class "Default")
      (node (ref "R192") (pin "1") (pinfunction "1_1") (pintype "passive"))
      (node (ref "U22") (pin "12") (pinfunction "0P1V_12") (pintype "passive"))
    )
    (net (code "26") (name "Net-(U22-0P2V)") (class "Default")
      (node (ref "R194") (pin "1") (pinfunction "1_1") (pintype "passive"))
      (node (ref "U22") (pin "11") (pinfunction "0P2V_11") (pintype "passive"))
    )
    (net (code "27") (name "Net-(U22-0P4V)") (class "Default")
      (node (ref "R199") (pin "1") (pinfunction "1_1") (pintype "passive"))
      (node (ref "U22") (pin "10") (pinfunction "0P4V_10") (pintype "passive"))
    )
    (net (code "28") (name "Net-(U22-0P8V)") (class "Default")
      (node (ref "R201") (pin "1") (pinfunction "1_1") (pintype "passive"))
      (node (ref "U22") (pin "9") (pinfunction "0P8V_9") (pintype "passive"))
    )
    (net (code "29") (name "Net-(U22-1P6V)") (class "Default")
      (node (ref "R203") (pin "1") (pinfunction "1_1") (pintype "passive"))
      (node (ref "U22") (pin "8") (pinfunction "1P6V_8") (pintype "passive"))
    )
    (net (code "30") (name "Net-(U22-3P2V)") (class "Default")
      (node (ref "R205") (pin "1") (pinfunction "1_1") (pintype "passive"))
      (node (ref "U22") (pin "6") (pinfunction "3P2V_6") (pintype "passive"))
    )
    (net (code "31") (name "Net-(U22-6P4V1)") (class "Default")
      (node (ref "R209") (pin "1") (pinfunction "1_1") (pintype "passive"))
      (node (ref "U22") (pin "5") (pinfunction "6P4V1_5") (pintype "passive"))
    )
    (net (code "32") (name "Net-(U22-6P4V2)") (class "Default")
      (node (ref "R211") (pin "1") (pinfunction "1_1") (pintype "passive"))
      (node (ref "U22") (pin "4") (pinfunction "6P4V2_4") (pintype "passive"))
    )
    (net (code "33") (name "Net-(U22-EN)") (class "Default")
      (node (ref "R189") (pin "1") (pinfunction "1_1") (pintype "passive"))
      (node (ref "U22") (pin "13") (pinfunction "EN_13") (pintype "passive"))
    )
    (net (code "34") (name "Net-(U22-NR)") (class "Default")
      (node (ref "C400") (pin "1") (pinfunction "1_1") (pintype "passive"))
      (node (ref "C401") (pin "1") (pinfunction "1_1") (pintype "passive"))
      (node (ref "U22") (pin "14") (pinfunction "NR_14") (pintype "passive"))
    )
    (net (code "35") (name "Net-(U23-0P1V)") (class "Default")
      (node (ref "R193") (pin "1") (pinfunction "1_1") (pintype "passive"))
      (node (ref "U23") (pin "12") (pinfunction "0P1V_12") (pintype "passive"))
    )
    (net (code "36") (name "Net-(U23-0P2V)") (class "Default")
      (node (ref "R195") (pin "1") (pinfunction "1_1") (pintype "passive"))
      (node (ref "U23") (pin "11") (pinfunction "0P2V_11") (pintype "passive"))
    )
    (net (code "37") (name "Net-(U23-0P4V)") (class "Default")
      (node (ref "R200") (pin "1") (pinfunction "1_1") (pintype "passive"))
      (node (ref "U23") (pin "10") (pinfunction "0P4V_10") (pintype "passive"))
    )
    (net (code "38") (name "Net-(U23-0P8V)") (class "Default")
      (node (ref "R202") (pin "1") (pinfunction "1_1") (pintype "passive"))
      (node (ref "U23") (pin "9") (pinfunction "0P8V_9") (pintype "passive"))
    )
    (net (code "39") (name "Net-(U23-1P6V)") (class "Default")
      (node (ref "R204") (pin "1") (pinfunction "1_1") (pintype "passive"))
      (node (ref "U23") (pin "8") (pinfunction "1P6V_8") (pintype "passive"))
    )
    (net (code "40") (name "Net-(U23-3P2V)") (class "Default")
      (node (ref "R206") (pin "1") (pinfunction "1_1") (pintype "passive"))
      (node (ref "U23") (pin "6") (pinfunction "3P2V_6") (pintype "passive"))
    )
    (net (code "41") (name "Net-(U23-6P4V1)") (class "Default")
      (node (ref "R210") (pin "1") (pinfunction "1_1") (pintype "passive"))
      (node (ref "U23") (pin "5") (pinfunction "6P4V1_5") (pintype "passive"))
    )
    (net (code "42") (name "Net-(U23-6P4V2)") (class "Default")
      (node (ref "R212") (pin "1") (pinfunction "1_1") (pintype "passive"))
      (node (ref "U23") (pin "4") (pinfunction "6P4V2_4") (pintype "passive"))
    )
    (net (code "43") (name "Net-(U23-EN)") (class "Default")
      (node (ref "R190") (pin "1") (pinfunction "1_1") (pintype "passive"))
      (node (ref "U23") (pin "13") (pinfunction "EN_13") (pintype "passive"))
    )
    (net (code "44") (name "Net-(U23-NR)") (class "Default")
      (node (ref "C403") (pin "1") (pinfunction "1_1") (pintype "passive"))
      (node (ref "C404") (pin "1") (pinfunction "1_1") (pintype "passive"))
      (node (ref "U23") (pin "14") (pinfunction "NR_14") (pintype "passive"))
    )
    (net (code "45") (name "Net-(U24-ADJ)") (class "Default")
      (node (ref "R216") (pin "1") (pinfunction "1_1") (pintype "passive"))
      (node (ref "U24") (pin "4") (pinfunction "ADJ_4") (pintype "passive"))
    )
    (net (code "46") (name "Net-(U24-INHIBIT)") (class "Default")
      (node (ref "R214") (pin "1") (pinfunction "1_1") (pintype "passive"))
      (node (ref "U24") (pin "3") (pinfunction "INHIBIT_3") (pintype "passive"))
    )
    (net (code "47") (name "Net-(U24-VIN)") (class "Default")
      (node (ref "NT43") (pin "1") (pinfunction "1_1") (pintype "passive"))
      (node (ref "R213") (pin "2") (pinfunction "2_2") (pintype "passive"))
      (node (ref "U24") (pin "2") (pinfunction "VIN_2") (pintype "passive"))
    )
    (net (code "48") (name "Net-(U25-EN)") (class "Default")
      (node (ref "R217") (pin "1") (pinfunction "1_1") (pintype "passive"))
      (node (ref "U25") (pin "13") (pinfunction "EN_13") (pintype "passive"))
    )
    (net (code "49") (name "Net-(U25-FB)") (class "Default")
      (node (ref "C412") (pin "2") (pinfunction "2_2") (pintype "passive"))
      (node (ref "R218") (pin "2") (pinfunction "2_2") (pintype "passive"))
      (node (ref "R220") (pin "1") (pinfunction "1_1") (pintype "passive"))
      (node (ref "U25") (pin "3") (pinfunction "FB_3") (pintype "passive"))
    )
    (net (code "50") (name "Net-(U25-NR{slash}SS)") (class "Default")
      (node (ref "C413") (pin "1") (pinfunction "1_1") (pintype "passive"))
      (node (ref "U25") (pin "14") (pinfunction "NR/SS_14") (pintype "passive"))
    )
  )
)
